# 4_Unextended55_periferals.net
KiCad netlist of a schematic drawn in Altium Designer
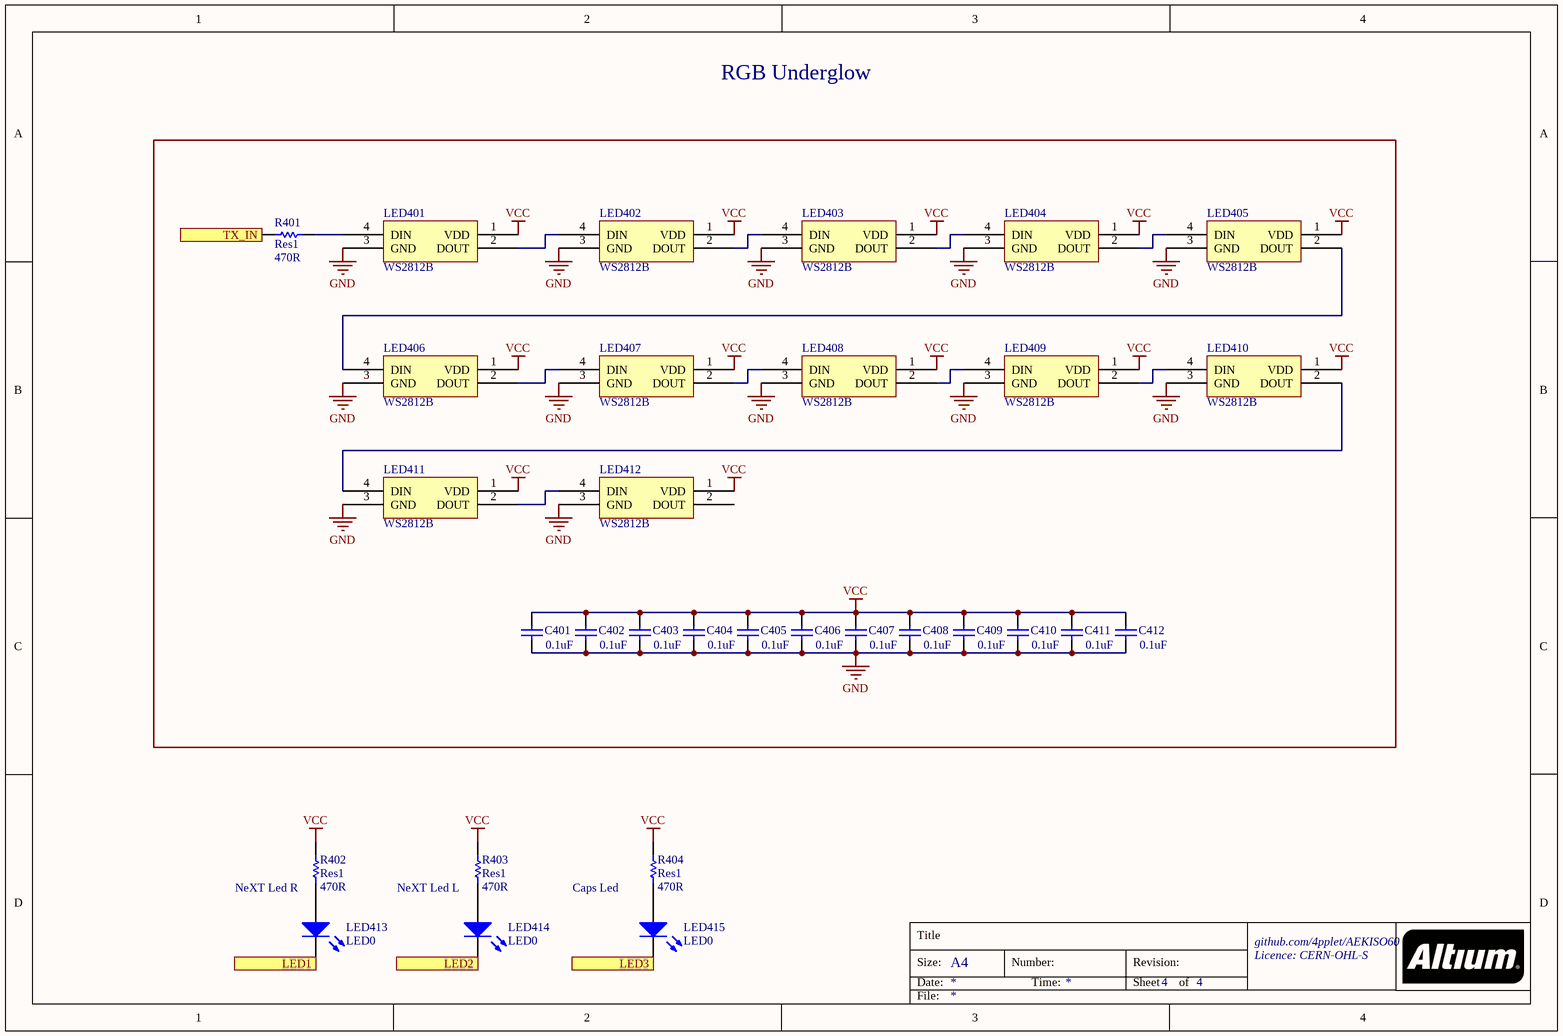
[diagram p0: 4_Unextended55_periferals.SchDoc]

(export (version "E")
  (design (tool "Eeschema 10.0.6"))
  (components
    (comp (ref "C401")
      (value "0.1uF")
      (footprint "C0603[1608]")
      (description "Capacitor")
      (fields (field (name "LCSC PART #") "C14663") (field (name "MRF.PART") "CC0603KRX7R9BB104"))
      (libsource (lib "Miscellaneous Devices") (part "Cap"))
    )
    (comp (ref "C402")
      (value "0.1uF")
      (footprint "C0603[1608]")
      (description "Capacitor")
      (fields (field (name "LCSC PART #") "C14663") (field (name "MRF.PART") "CC0603KRX7R9BB104"))
      (libsource (lib "Miscellaneous Devices") (part "Cap"))
    )
    (comp (ref "C403")
      (value "0.1uF")
      (footprint "C0603[1608]")
      (description "Capacitor")
      (fields (field (name "LCSC PART #") "C14663") (field (name "MRF.PART") "CC0603KRX7R9BB104"))
      (libsource (lib "Miscellaneous Devices") (part "Cap"))
    )
    (comp (ref "C404")
      (value "0.1uF")
      (footprint "C0603[1608]")
      (description "Capacitor")
      (fields (field (name "LCSC PART #") "C14663") (field (name "MRF.PART") "CC0603KRX7R9BB104"))
      (libsource (lib "Miscellaneous Devices") (part "Cap"))
    )
    (comp (ref "C405")
      (value "0.1uF")
      (footprint "C0603[1608]")
      (description "Capacitor")
      (fields (field (name "LCSC PART #") "C14663") (field (name "MRF.PART") "CC0603KRX7R9BB104"))
      (libsource (lib "Miscellaneous Devices") (part "Cap"))
    )
    (comp (ref "C406")
      (value "0.1uF")
      (footprint "C0603[1608]")
      (description "Capacitor")
      (fields (field (name "LCSC PART #") "C14663") (field (name "MRF.PART") "CC0603KRX7R9BB104"))
      (libsource (lib "Miscellaneous Devices") (part "Cap"))
    )
    (comp (ref "C407")
      (value "0.1uF")
      (footprint "C0603[1608]")
      (description "Capacitor")
      (fields (field (name "LCSC PART #") "C14663") (field (name "MRF.PART") "CC0603KRX7R9BB104"))
      (libsource (lib "Miscellaneous Devices") (part "Cap"))
    )
    (comp (ref "C408")
      (value "0.1uF")
      (footprint "C0603[1608]")
      (description "Capacitor")
      (fields (field (name "LCSC PART #") "C14663") (field (name "MRF.PART") "CC0603KRX7R9BB104"))
      (libsource (lib "Miscellaneous Devices") (part "Cap"))
    )
    (comp (ref "C409")
      (value "0.1uF")
      (footprint "C0603[1608]")
      (description "Capacitor")
      (fields (field (name "LCSC PART #") "C14663") (field (name "MRF.PART") "CC0603KRX7R9BB104"))
      (libsource (lib "Miscellaneous Devices") (part "Cap"))
    )
    (comp (ref "C410")
      (value "0.1uF")
      (footprint "C0603[1608]")
      (description "Capacitor")
      (fields (field (name "LCSC PART #") "C14663") (field (name "MRF.PART") "CC0603KRX7R9BB104"))
      (libsource (lib "Miscellaneous Devices") (part "Cap"))
    )
    (comp (ref "C411")
      (value "0.1uF")
      (footprint "C0603[1608]")
      (description "Capacitor")
      (fields (field (name "LCSC PART #") "C14663") (field (name "MRF.PART") "CC0603KRX7R9BB104"))
      (libsource (lib "Miscellaneous Devices") (part "Cap"))
    )
    (comp (ref "C412")
      (value "0.1uF")
      (footprint "C0603[1608]")
      (description "Capacitor")
      (fields (field (name "LCSC PART #") "C14663") (field (name "MRF.PART") "CC0603KRX7R9BB104"))
      (libsource (lib "Miscellaneous Devices") (part "Cap"))
    )
    (comp (ref "LED401")
      (value "WS2812B")
      (footprint "WS2812B - 5050")
      (fields (field (name "LCSC PART #") "C2874885") (field (name "MRF.PART") "WS2812B-V5/W"))
      (libsource (lib "Keebs") (part "WS2812B"))
    )
    (comp (ref "LED402")
      (value "WS2812B")
      (footprint "WS2812B - 5050")
      (fields (field (name "LCSC PART #") "C2874885") (field (name "MRF.PART") "WS2812B-V5/W"))
      (libsource (lib "Keebs") (part "WS2812B"))
    )
    (comp (ref "LED403")
      (value "WS2812B")
      (footprint "WS2812B - 5050")
      (fields (field (name "LCSC PART #") "C2874885") (field (name "MRF.PART") "WS2812B-V5/W"))
      (libsource (lib "Keebs") (part "WS2812B"))
    )
    (comp (ref "LED404")
      (value "WS2812B")
      (footprint "WS2812B - 5050")
      (fields (field (name "LCSC PART #") "C2874885") (field (name "MRF.PART") "WS2812B-V5/W"))
      (libsource (lib "Keebs") (part "WS2812B"))
    )
    (comp (ref "LED405")
      (value "WS2812B")
      (footprint "WS2812B - 5050")
      (fields (field (name "LCSC PART #") "C2874885") (field (name "MRF.PART") "WS2812B-V5/W"))
      (libsource (lib "Keebs") (part "WS2812B"))
    )
    (comp (ref "LED406")
      (value "WS2812B")
      (footprint "WS2812B - 5050")
      (fields (field (name "LCSC PART #") "C2874885") (field (name "MRF.PART") "WS2812B-V5/W"))
      (libsource (lib "Keebs") (part "WS2812B"))
    )
    (comp (ref "LED407")
      (value "WS2812B")
      (footprint "WS2812B - 5050")
      (fields (field (name "LCSC PART #") "C2874885") (field (name "MRF.PART") "WS2812B-V5/W"))
      (libsource (lib "Keebs") (part "WS2812B"))
    )
    (comp (ref "LED408")
      (value "WS2812B")
      (footprint "WS2812B - 5050")
      (fields (field (name "LCSC PART #") "C2874885") (field (name "MRF.PART") "WS2812B-V5/W"))
      (libsource (lib "Keebs") (part "WS2812B"))
    )
    (comp (ref "LED409")
      (value "WS2812B")
      (footprint "WS2812B - 5050")
      (fields (field (name "LCSC PART #") "C2874885") (field (name "MRF.PART") "WS2812B-V5/W"))
      (libsource (lib "Keebs") (part "WS2812B"))
    )
    (comp (ref "LED410")
      (value "WS2812B")
      (footprint "WS2812B - 5050")
      (fields (field (name "LCSC PART #") "C2874885") (field (name "MRF.PART") "WS2812B-V5/W"))
      (libsource (lib "Keebs") (part "WS2812B"))
    )
    (comp (ref "LED411")
      (value "WS2812B")
      (footprint "WS2812B - 5050")
      (fields (field (name "LCSC PART #") "C2874885") (field (name "MRF.PART") "WS2812B-V5/W"))
      (libsource (lib "Keebs") (part "WS2812B"))
    )
    (comp (ref "LED412")
      (value "WS2812B")
      (footprint "WS2812B - 5050")
      (fields (field (name "LCSC PART #") "C2874885") (field (name "MRF.PART") "WS2812B-V5/W"))
      (libsource (lib "Keebs") (part "WS2812B"))
    )
    (comp (ref "LED413")
      (value "LED0")
      (footprint "SWITCH_LED - 1U")
      (description "Typical INFRARED GaAs LED")
      (libsource (lib "Miscellaneous Devices") (part "LED0"))
    )
    (comp (ref "LED414")
      (value "LED0")
      (footprint "SWITCH_LED - 1U")
      (description "Typical INFRARED GaAs LED")
      (libsource (lib "Miscellaneous Devices") (part "LED0"))
    )
    (comp (ref "LED415")
      (value "LED0")
      (footprint "SWITCH_LED - 1U")
      (description "Typical INFRARED GaAs LED")
      (libsource (lib "Miscellaneous Devices") (part "LED0"))
    )
    (comp (ref "R401")
      (value "Res1")
      (footprint "R0603[1608]")
      (description "Resistor")
      (fields
        (field (name "ALTIUM_VALUE") "470R")
        (field (name "LCSC PART #") "C23179")
        (field (name "MRF.PART") "0603WAF4700T5E")
      )
      (libsource (lib "Miscellaneous Devices") (part "Res1"))
    )
    (comp (ref "R402")
      (value "Res1")
      (footprint "R0603[1608] - THT")
      (description "Resistor")
      (fields
        (field (name "ALTIUM_VALUE") "470R")
        (field (name "LCSC PART #") "C23179")
        (field (name "MRF.PART") "0603WAF4700T5E")
      )
      (libsource (lib "Miscellaneous Devices") (part "Res1"))
    )
    (comp (ref "R403")
      (value "Res1")
      (footprint "R0603[1608] - THT")
      (description "Resistor")
      (fields
        (field (name "ALTIUM_VALUE") "470R")
        (field (name "LCSC PART #") "C23179")
        (field (name "MRF.PART") "0603WAF4700T5E")
      )
      (libsource (lib "Miscellaneous Devices") (part "Res1"))
    )
    (comp (ref "R404")
      (value "Res1")
      (footprint "R0603[1608] - THT")
      (description "Resistor")
      (fields
        (field (name "ALTIUM_VALUE") "470R")
        (field (name "LCSC PART #") "C23179")
        (field (name "MRF.PART") "0603WAF4700T5E")
      )
      (libsource (lib "Miscellaneous Devices") (part "Res1"))
    )
  )
  (nets
    (net (code "1") (name "/LED1") (class "Default")
      (node (ref "LED413") (pin "2") (pinfunction "K_2") (pintype "passive"))
    )
    (net (code "2") (name "/LED2") (class "Default")
      (node (ref "LED414") (pin "2") (pinfunction "K_2") (pintype "passive"))
    )
    (net (code "3") (name "/LED3") (class "Default")
      (node (ref "LED415") (pin "2") (pinfunction "K_2") (pintype "passive"))
    )
    (net (code "4") (name "/TX_IN") (class "Default")
      (node (ref "R401") (pin "1") (pinfunction "1_1") (pintype "passive"))
    )
    (net (code "5") (name "GND") (class "Default")
      (node (ref "C401") (pin "1") (pinfunction "1_1") (pintype "passive"))
      (node (ref "C402") (pin "1") (pinfunction "1_1") (pintype "passive"))
      (node (ref "C403") (pin "1") (pinfunction "1_1") (pintype "passive"))
      (node (ref "C404") (pin "1") (pinfunction "1_1") (pintype "passive"))
      (node (ref "C405") (pin "1") (pinfunction "1_1") (pintype "passive"))
      (node (ref "C406") (pin "1") (pinfunction "1_1") (pintype "passive"))
      (node (ref "C407") (pin "1") (pinfunction "1_1") (pintype "passive"))
      (node (ref "C408") (pin "1") (pinfunction "1_1") (pintype "passive"))
      (node (ref "C409") (pin "1") (pinfunction "1_1") (pintype "passive"))
      (node (ref "C410") (pin "1") (pinfunction "1_1") (pintype "passive"))
      (node (ref "C411") (pin "1") (pinfunction "1_1") (pintype "passive"))
      (node (ref "C412") (pin "1") (pinfunction "1_1") (pintype "passive"))
      (node (ref "LED401") (pin "3") (pinfunction "GND_3") (pintype "passive"))
      (node (ref "LED402") (pin "3") (pinfunction "GND_3") (pintype "passive"))
      (node (ref "LED403") (pin "3") (pinfunction "GND_3") (pintype "passive"))
      (node (ref "LED404") (pin "3") (pinfunction "GND_3") (pintype "passive"))
      (node (ref "LED405") (pin "3") (pinfunction "GND_3") (pintype "passive"))
      (node (ref "LED406") (pin "3") (pinfunction "GND_3") (pintype "passive"))
      (node (ref "LED407") (pin "3") (pinfunction "GND_3") (pintype "passive"))
      (node (ref "LED408") (pin "3") (pinfunction "GND_3") (pintype "passive"))
      (node (ref "LED409") (pin "3") (pinfunction "GND_3") (pintype "passive"))
      (node (ref "LED410") (pin "3") (pinfunction "GND_3") (pintype "passive"))
      (node (ref "LED411") (pin "3") (pinfunction "GND_3") (pintype "passive"))
      (node (ref "LED412") (pin "3") (pinfunction "GND_3") (pintype "passive"))
    )
    (net (code "6") (name "Net-(LED401-DIN)") (class "Default")
      (node (ref "LED401") (pin "4") (pinfunction "DIN_4") (pintype "passive"))
      (node (ref "R401") (pin "2") (pinfunction "2_2") (pintype "passive"))
    )
    (net (code "7") (name "Net-(LED401-DOUT)") (class "Default")
      (node (ref "LED401") (pin "2") (pinfunction "DOUT_2") (pintype "passive"))
      (node (ref "LED402") (pin "4") (pinfunction "DIN_4") (pintype "passive"))
    )
    (net (code "8") (name "Net-(LED402-DOUT)") (class "Default")
      (node (ref "LED402") (pin "2") (pinfunction "DOUT_2") (pintype "passive"))
      (node (ref "LED403") (pin "4") (pinfunction "DIN_4") (pintype "passive"))
    )
    (net (code "9") (name "Net-(LED403-DOUT)") (class "Default")
      (node (ref "LED403") (pin "2") (pinfunction "DOUT_2") (pintype "passive"))
      (node (ref "LED404") (pin "4") (pinfunction "DIN_4") (pintype "passive"))
    )
    (net (code "10") (name "Net-(LED404-DOUT)") (class "Default")
      (node (ref "LED404") (pin "2") (pinfunction "DOUT_2") (pintype "passive"))
      (node (ref "LED405") (pin "4") (pinfunction "DIN_4") (pintype "passive"))
    )
    (net (code "11") (name "Net-(LED405-DOUT)") (class "Default")
      (node (ref "LED405") (pin "2") (pinfunction "DOUT_2") (pintype "passive"))
      (node (ref "LED406") (pin "4") (pinfunction "DIN_4") (pintype "passive"))
    )
    (net (code "12") (name "Net-(LED406-DOUT)") (class "Default")
      (node (ref "LED406") (pin "2") (pinfunction "DOUT_2") (pintype "passive"))
      (node (ref "LED407") (pin "4") (pinfunction "DIN_4") (pintype "passive"))
    )
    (net (code "13") (name "Net-(LED407-DOUT)") (class "Default")
      (node (ref "LED407") (pin "2") (pinfunction "DOUT_2") (pintype "passive"))
      (node (ref "LED408") (pin "4") (pinfunction "DIN_4") (pintype "passive"))
    )
    (net (code "14") (name "Net-(LED408-DOUT)") (class "Default")
      (node (ref "LED408") (pin "2") (pinfunction "DOUT_2") (pintype "passive"))
      (node (ref "LED409") (pin "4") (pinfunction "DIN_4") (pintype "passive"))
    )
    (net (code "15") (name "Net-(LED409-DOUT)") (class "Default")
      (node (ref "LED409") (pin "2") (pinfunction "DOUT_2") (pintype "passive"))
      (node (ref "LED410") (pin "4") (pinfunction "DIN_4") (pintype "passive"))
    )
    (net (code "16") (name "Net-(LED410-DOUT)") (class "Default")
      (node (ref "LED410") (pin "2") (pinfunction "DOUT_2") (pintype "passive"))
      (node (ref "LED411") (pin "4") (pinfunction "DIN_4") (pintype "passive"))
    )
    (net (code "17") (name "Net-(LED411-DOUT)") (class "Default")
      (node (ref "LED411") (pin "2") (pinfunction "DOUT_2") (pintype "passive"))
      (node (ref "LED412") (pin "4") (pinfunction "DIN_4") (pintype "passive"))
    )
    (net (code "18") (name "Net-(LED413-A)") (class "Default")
      (node (ref "LED413") (pin "1") (pinfunction "A_1") (pintype "passive"))
      (node (ref "R402") (pin "1") (pinfunction "1_1") (pintype "passive"))
    )
    (net (code "19") (name "Net-(LED414-A)") (class "Default")
      (node (ref "LED414") (pin "1") (pinfunction "A_1") (pintype "passive"))
      (node (ref "R403") (pin "1") (pinfunction "1_1") (pintype "passive"))
    )
    (net (code "20") (name "Net-(LED415-A)") (class "Default")
      (node (ref "LED415") (pin "1") (pinfunction "A_1") (pintype "passive"))
      (node (ref "R404") (pin "1") (pinfunction "1_1") (pintype "passive"))
    )
    (net (code "21") (name "VCC") (class "Default")
      (node (ref "C401") (pin "2") (pinfunction "2_2") (pintype "passive"))
      (node (ref "C402") (pin "2") (pinfunction "2_2") (pintype "passive"))
      (node (ref "C403") (pin "2") (pinfunction "2_2") (pintype "passive"))
      (node (ref "C404") (pin "2") (pinfunction "2_2") (pintype "passive"))
      (node (ref "C405") (pin "2") (pinfunction "2_2") (pintype "passive"))
      (node (ref "C406") (pin "2") (pinfunction "2_2") (pintype "passive"))
      (node (ref "C407") (pin "2") (pinfunction "2_2") (pintype "passive"))
      (node (ref "C408") (pin "2") (pinfunction "2_2") (pintype "passive"))
      (node (ref "C409") (pin "2") (pinfunction "2_2") (pintype "passive"))
      (node (ref "C410") (pin "2") (pinfunction "2_2") (pintype "passive"))
      (node (ref "C411") (pin "2") (pinfunction "2_2") (pintype "passive"))
      (node (ref "C412") (pin "2") (pinfunction "2_2") (pintype "passive"))
      (node (ref "LED401") (pin "1") (pinfunction "VDD_1") (pintype "passive"))
      (node (ref "LED402") (pin "1") (pinfunction "VDD_1") (pintype "passive"))
      (node (ref "LED403") (pin "1") (pinfunction "VDD_1") (pintype "passive"))
      (node (ref "LED404") (pin "1") (pinfunction "VDD_1") (pintype "passive"))
      (node (ref "LED405") (pin "1") (pinfunction "VDD_1") (pintype "passive"))
      (node (ref "LED406") (pin "1") (pinfunction "VDD_1") (pintype "passive"))
      (node (ref "LED407") (pin "1") (pinfunction "VDD_1") (pintype "passive"))
      (node (ref "LED408") (pin "1") (pinfunction "VDD_1") (pintype "passive"))
      (node (ref "LED409") (pin "1") (pinfunction "VDD_1") (pintype "passive"))
      (node (ref "LED410") (pin "1") (pinfunction "VDD_1") (pintype "passive"))
      (node (ref "LED411") (pin "1") (pinfunction "VDD_1") (pintype "passive"))
      (node (ref "LED412") (pin "1") (pinfunction "VDD_1") (pintype "passive"))
      (node (ref "R402") (pin "2") (pinfunction "2_2") (pintype "passive"))
      (node (ref "R403") (pin "2") (pinfunction "2_2") (pintype "passive"))
      (node (ref "R404") (pin "2") (pinfunction "2_2") (pintype "passive"))
    )
    (net (code "22") (name "unconnected-(LED412-DOUT-Pad2)") (class "Default")
      (node (ref "LED412") (pin "2") (pinfunction "DOUT_2") (pintype "passive"))
    )
  )
)
